# other.net
KiCad netlist of a schematic drawn in Altium Designer
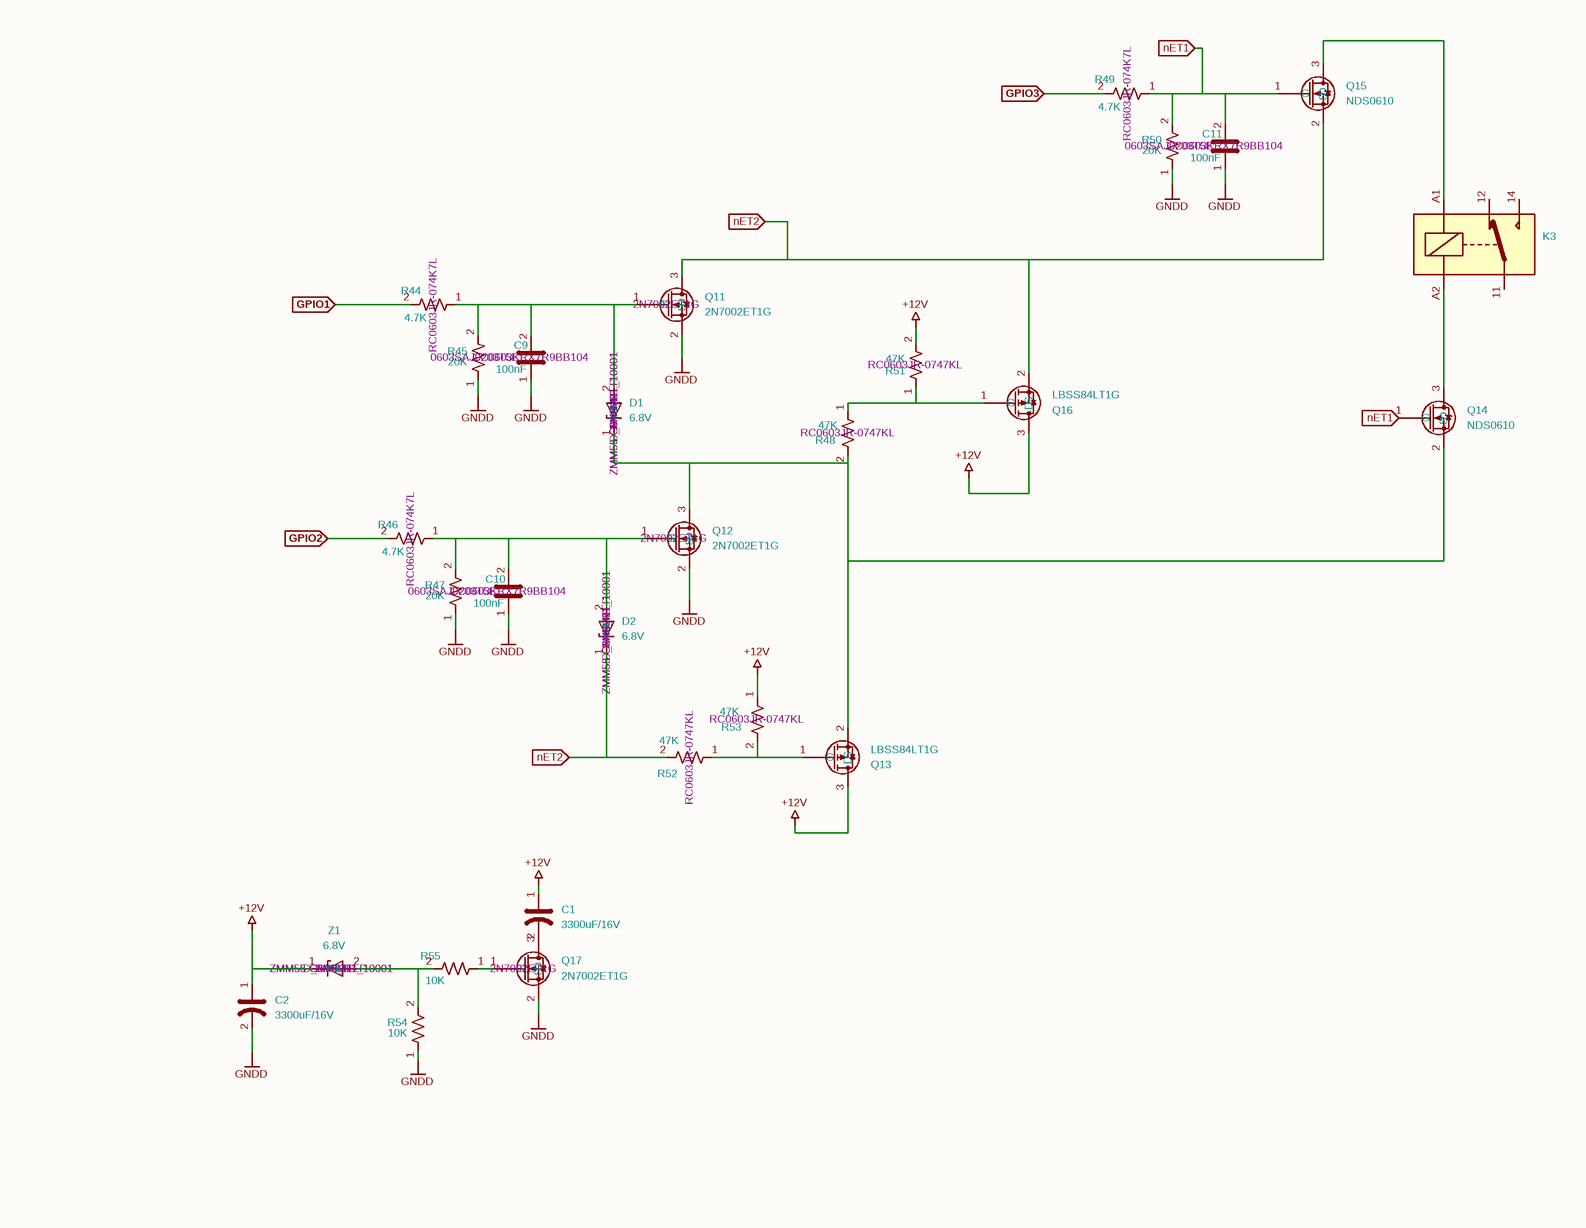
[diagram p0: other.SchDoc, left]
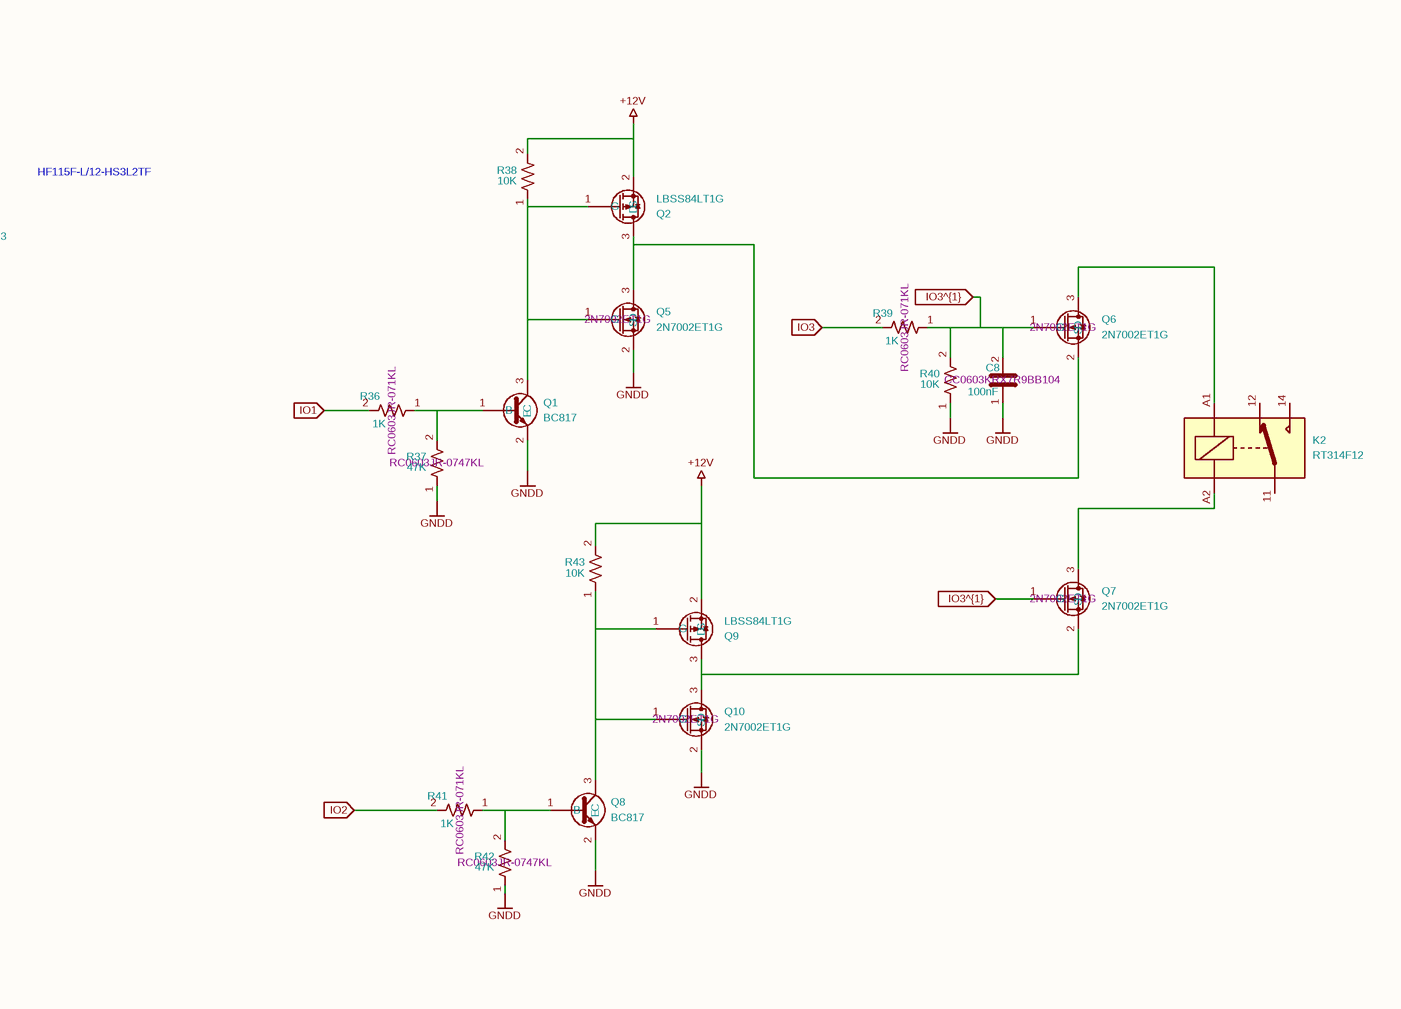
[diagram p1: other.SchDoc, right]

(export (version "E")
  (design (tool "Eeschema 10.0.6"))
  (components
    (comp (ref "C1")
      (value "3300uF/16V")
      (description "capacitor, US symbol")
      (libsource (lib "Device") (part "C_US"))
    )
    (comp (ref "C2")
      (value "3300uF/16V")
      (description "capacitor, US symbol")
      (libsource (lib "Device") (part "C_US"))
    )
    (comp (ref "C8")
      (value "100nF")
      (footprint "C_0603_1608Metric")
      (description "CAP CER 100nF 50V X7R 0603")
      (fields
        (field (name "MP") "CC0603KRX7R9BB104")
        (field (name "MF") "YAGEO")
        (field (name "OZD") "CC0603KRX7R9BB104")
      )
      (libsource (lib "*") (part "C_3"))
    )
    (comp (ref "C9")
      (value "100nF")
      (footprint "C_0603_1608Metric")
      (description "CAP CER 100nF 50V X7R 0603")
      (fields
        (field (name "MP") "CC0603KRX7R9BB104")
        (field (name "MF") "YAGEO")
        (field (name "OZD") "CC0603KRX7R9BB104")
      )
      (libsource (lib "*") (part "C_3"))
    )
    (comp (ref "C10")
      (value "100nF")
      (footprint "C_0603_1608Metric")
      (description "CAP CER 100nF 50V X7R 0603")
      (fields
        (field (name "MP") "CC0603KRX7R9BB104")
        (field (name "MF") "YAGEO")
        (field (name "OZD") "CC0603KRX7R9BB104")
      )
      (libsource (lib "*") (part "C_3"))
    )
    (comp (ref "C11")
      (value "100nF")
      (footprint "C_0603_1608Metric")
      (description "CAP CER 100nF 50V X7R 0603")
      (fields
        (field (name "MP") "CC0603KRX7R9BB104")
        (field (name "MF") "YAGEO")
        (field (name "OZD") "CC0603KRX7R9BB104")
      )
      (libsource (lib "*") (part "C_3"))
    )
    (comp (ref "D1")
      (value "6.8V")
      (description "DIODE ZENER 500mW 6.8V ±5% SOD80 (MINIMELF) SMT")
      (fields
        (field (name "MF") "PANJIT")
        (field (name "MP") "ZMM55-C6V8_R1_10001")
        (field (name "OZD") "ZMM55-C6V8_R1_10001")
        (field (name "PACKAGE") "D_MiniMELF")
      )
      (libsource (lib "*") (part "D_Zener_1"))
    )
    (comp (ref "D2")
      (value "6.8V")
      (description "DIODE ZENER 500mW 6.8V ±5% SOD80 (MINIMELF) SMT")
      (fields
        (field (name "MF") "PANJIT")
        (field (name "MP") "ZMM55-C6V8_R1_10001")
        (field (name "OZD") "ZMM55-C6V8_R1_10001")
        (field (name "PACKAGE") "D_MiniMELF")
      )
      (libsource (lib "Device") (part "D_Zener"))
    )
    (comp (ref "K2")
      (value "RT314F12")
      (footprint "RELAY9-500X1142_618")
      (description "RELAY POWER SPDT-CO 16A 12V")
      (fields (field (name "MF") "TE Connectivity"))
      (libsource (lib "*") (part "RT314A03_1"))
    )
    (comp (ref "K3")
      (value "RT314F12")
      (footprint "RELAY9-500X1142_618")
      (description "RELAY POWER SPDT-CO 16A 12V")
      (fields (field (name "MF") "TE Connectivity"))
      (libsource (lib "*") (part "RT314A03_1"))
    )
    (comp (ref "Q1")
      (value "BC817")
      (footprint "SOT-23")
      (description "0.8A Ic, 45V Vce, NPN Transistor, SOT-23")
      (libsource (lib "Transistor_BJT") (part "BC817"))
    )
    (comp (ref "Q2")
      (value "LBSS84LT1G")
      (footprint "SOT-23")
      (description "P-MOSFET transistor, gate/source/drain")
      (libsource (lib "Transistor_FET") (part "Q_PMOS_GSD"))
    )
    (comp (ref "Q5")
      (value "2N7002ET1G")
      (footprint "SOT-23")
      (description "MOSFET N-CH 60V 310mA SOT-23")
      (fields (field (name "MF") "onsemi") (field (name "OZD") "2N7002ET1G"))
      (libsource (lib "Transistor_FET_Other") (part "Q_NMOS_Depletion_GSD"))
    )
    (comp (ref "Q6")
      (value "2N7002ET1G")
      (footprint "SOT-23")
      (description "MOSFET N-CH 60V 310mA SOT-23")
      (fields (field (name "MF") "onsemi") (field (name "OZD") "2N7002ET1G"))
      (libsource (lib "Transistor_FET_Other") (part "Q_NMOS_Depletion_GSD"))
    )
    (comp (ref "Q7")
      (value "2N7002ET1G")
      (footprint "SOT-23")
      (description "MOSFET N-CH 60V 310mA SOT-23")
      (fields (field (name "MF") "onsemi") (field (name "OZD") "2N7002ET1G"))
      (libsource (lib "Transistor_FET_Other") (part "Q_NMOS_Depletion_GSD"))
    )
    (comp (ref "Q8")
      (value "BC817")
      (footprint "SOT-23")
      (description "0.8A Ic, 45V Vce, NPN Transistor, SOT-23")
      (libsource (lib "Transistor_BJT") (part "BC817"))
    )
    (comp (ref "Q9")
      (value "LBSS84LT1G")
      (footprint "SOT-23")
      (description "P-MOSFET transistor, gate/source/drain")
      (libsource (lib "Transistor_FET") (part "Q_PMOS_GSD"))
    )
    (comp (ref "Q10")
      (value "2N7002ET1G")
      (footprint "SOT-23")
      (description "MOSFET N-CH 60V 310mA SOT-23")
      (fields (field (name "MF") "onsemi") (field (name "OZD") "2N7002ET1G"))
      (libsource (lib "Transistor_FET_Other") (part "Q_NMOS_Depletion_GSD"))
    )
    (comp (ref "Q11")
      (value "2N7002ET1G")
      (footprint "SOT-23")
      (description "MOSFET N-CH 60V 310mA SOT-23")
      (fields (field (name "MF") "onsemi") (field (name "OZD") "2N7002ET1G"))
      (libsource (lib "Transistor_FET_Other") (part "Q_NMOS_Depletion_GSD"))
    )
    (comp (ref "Q12")
      (value "2N7002ET1G")
      (footprint "SOT-23")
      (description "MOSFET N-CH 60V 310mA SOT-23")
      (fields (field (name "MF") "onsemi") (field (name "OZD") "2N7002ET1G"))
      (libsource (lib "Transistor_FET_Other") (part "Q_NMOS_Depletion_GSD"))
    )
    (comp (ref "Q13")
      (value "LBSS84LT1G")
      (footprint "SOT-23")
      (description "P-MOSFET transistor, gate/source/drain")
      (libsource (lib "Transistor_FET") (part "Q_PMOS_GSD"))
    )
    (comp (ref "Q14")
      (value "NDS0610")
      (footprint "SOT-23")
      (libsource (lib "Transistor_FET_Other") (part "Q_NMOS_Depletion_GSD"))
    )
    (comp (ref "Q15")
      (value "NDS0610")
      (footprint "SOT-23")
      (libsource (lib "Transistor_FET_Other") (part "Q_NMOS_Depletion_GSD"))
    )
    (comp (ref "Q16")
      (value "LBSS84LT1G")
      (footprint "SOT-23")
      (description "P-MOSFET transistor, gate/source/drain")
      (libsource (lib "*") (part "Q_PMOS_GSD_1"))
    )
    (comp (ref "Q17")
      (value "2N7002ET1G")
      (footprint "SOT-23")
      (description "MOSFET N-CH 60V 310mA SOT-23")
      (fields (field (name "MF") "onsemi") (field (name "OZD") "2N7002ET1G"))
      (libsource (lib "Transistor_FET_Other") (part "Q_NMOS_Depletion_GSD"))
    )
    (comp (ref "R36")
      (value "1K")
      (footprint "R_0603_1608Metric")
      (description "RES 1kΩ ±5% 100mW 0603")
      (fields
        (field (name "MP") "RC0603JR-071KL")
        (field (name "MF") "YAGEO")
        (field (name "OZD") "RC0603JR-071KL")
      )
      (libsource (lib "Device") (part "R_US"))
    )
    (comp (ref "R37")
      (value "47K")
      (footprint "R_0603_1608Metric")
      (description "RES 47kΩ ±5% 100mW 0603")
      (fields
        (field (name "MP") "RC0603JR-0747KL")
        (field (name "MF") "YAGEO")
        (field (name "OZD") "RC0603JR-0747KL")
      )
      (libsource (lib "Device") (part "R_US"))
    )
    (comp (ref "R38")
      (value "10K")
      (footprint "R_0603_1608Metric")
      (description "100mW Thick Film Resistors 75V ±100ppm/℃ ±5% 10kΩ 0603 Chip Resistor - Surface Mount ROHS")
      (fields (field (name "MP") "FRC0603J103TS") (field (name "MF") "FOJAN"))
      (libsource (lib "Device") (part "R_US"))
    )
    (comp (ref "R39")
      (value "1K")
      (footprint "R_0603_1608Metric")
      (description "RES 1kΩ ±5% 100mW 0603")
      (fields
        (field (name "MP") "RC0603JR-071KL")
        (field (name "MF") "YAGEO")
        (field (name "OZD") "RC0603JR-071KL")
      )
      (libsource (lib "Device") (part "R_US"))
    )
    (comp (ref "R40")
      (value "10K")
      (footprint "R_0603_1608Metric")
      (description "100mW Thick Film Resistors 75V ±100ppm/℃ ±5% 10kΩ 0603 Chip Resistor - Surface Mount ROHS")
      (fields (field (name "MP") "FRC0603J103TS") (field (name "MF") "FOJAN"))
      (libsource (lib "Device") (part "R_US"))
    )
    (comp (ref "R41")
      (value "1K")
      (footprint "R_0603_1608Metric")
      (description "RES 1kΩ ±5% 100mW 0603")
      (fields
        (field (name "MP") "RC0603JR-071KL")
        (field (name "MF") "YAGEO")
        (field (name "OZD") "RC0603JR-071KL")
      )
      (libsource (lib "Device") (part "R_US"))
    )
    (comp (ref "R42")
      (value "47K")
      (footprint "R_0603_1608Metric")
      (description "RES 47kΩ ±5% 100mW 0603")
      (fields
        (field (name "MP") "RC0603JR-0747KL")
        (field (name "MF") "YAGEO")
        (field (name "OZD") "RC0603JR-0747KL")
      )
      (libsource (lib "Device") (part "R_US"))
    )
    (comp (ref "R43")
      (value "10K")
      (footprint "R_0603_1608Metric")
      (description "100mW Thick Film Resistors 75V ±100ppm/℃ ±5% 10kΩ 0603 Chip Resistor - Surface Mount ROHS")
      (fields (field (name "MP") "FRC0603J103TS") (field (name "MF") "FOJAN"))
      (libsource (lib "Device") (part "R_US"))
    )
    (comp (ref "R44")
      (value "4.7K")
      (footprint "R_0603_1608Metric")
      (description "RES 4.7kΩ ±5% 100mW 0603")
      (fields
        (field (name "MP") "RC0603JR-074K7L")
        (field (name "MF") "YAGEO")
        (field (name "OZD") "RC0603JR-074K7L")
      )
      (libsource (lib "Device") (part "R_US"))
    )
    (comp (ref "R45")
      (value "20K")
      (footprint "R_0603_1608Metric")
      (description "RES.(1608) 0603 20K Ohms 5% 1/10W-S 100PPM")
      (fields
        (field (name "MP") "0603SAJ0203T5E")
        (field (name "MF") "ROYALOHM")
        (field (name "OZD") "0603SAJ0203T5E")
      )
      (libsource (lib "Device") (part "R_US"))
    )
    (comp (ref "R46")
      (value "4.7K")
      (footprint "R_0603_1608Metric")
      (description "RES 4.7kΩ ±5% 100mW 0603")
      (fields
        (field (name "MP") "RC0603JR-074K7L")
        (field (name "MF") "YAGEO")
        (field (name "OZD") "RC0603JR-074K7L")
      )
      (libsource (lib "Device") (part "R_US"))
    )
    (comp (ref "R47")
      (value "20K")
      (footprint "R_0603_1608Metric")
      (description "RES.(1608) 0603 20K Ohms 5% 1/10W-S 100PPM")
      (fields
        (field (name "MP") "0603SAJ0203T5E")
        (field (name "MF") "ROYALOHM")
        (field (name "OZD") "0603SAJ0203T5E")
      )
      (libsource (lib "Device") (part "R_US"))
    )
    (comp (ref "R48")
      (value "47K")
      (footprint "R_0603_1608Metric")
      (description "RES 47kΩ ±5% 100mW 0603")
      (fields
        (field (name "MP") "RC0603JR-0747KL")
        (field (name "MF") "YAGEO")
        (field (name "OZD") "RC0603JR-0747KL")
      )
      (libsource (lib "Device") (part "R_US"))
    )
    (comp (ref "R49")
      (value "4.7K")
      (footprint "R_0603_1608Metric")
      (description "RES 4.7kΩ ±5% 100mW 0603")
      (fields
        (field (name "MP") "RC0603JR-074K7L")
        (field (name "MF") "YAGEO")
        (field (name "OZD") "RC0603JR-074K7L")
      )
      (libsource (lib "Device") (part "R_US"))
    )
    (comp (ref "R50")
      (value "20K")
      (footprint "R_0603_1608Metric")
      (description "RES.(1608) 0603 20K Ohms 5% 1/10W-S 100PPM")
      (fields
        (field (name "MP") "0603SAJ0203T5E")
        (field (name "MF") "ROYALOHM")
        (field (name "OZD") "0603SAJ0203T5E")
      )
      (libsource (lib "Device") (part "R_US"))
    )
    (comp (ref "R51")
      (value "47K")
      (footprint "R_0603_1608Metric")
      (description "RES 47kΩ ±5% 100mW 0603")
      (fields
        (field (name "MP") "RC0603JR-0747KL")
        (field (name "MF") "YAGEO")
        (field (name "OZD") "RC0603JR-0747KL")
      )
      (libsource (lib "Device") (part "R_US"))
    )
    (comp (ref "R52")
      (value "47K")
      (footprint "R_0603_1608Metric")
      (description "RES 47kΩ ±5% 100mW 0603")
      (fields
        (field (name "MP") "RC0603JR-0747KL")
        (field (name "MF") "YAGEO")
        (field (name "OZD") "RC0603JR-0747KL")
      )
      (libsource (lib "Device") (part "R_US"))
    )
    (comp (ref "R53")
      (value "47K")
      (footprint "R_0603_1608Metric")
      (description "RES 47kΩ ±5% 100mW 0603")
      (fields
        (field (name "MP") "RC0603JR-0747KL")
        (field (name "MF") "YAGEO")
        (field (name "OZD") "RC0603JR-0747KL")
      )
      (libsource (lib "Device") (part "R_US"))
    )
    (comp (ref "R54")
      (value "10K")
      (footprint "R_0603_1608Metric")
      (description "100mW Thick Film Resistors 75V ±100ppm/℃ ±5% 10kΩ 0603 Chip Resistor - Surface Mount ROHS")
      (fields (field (name "MP") "FRC0603J103TS") (field (name "MF") "FOJAN"))
      (libsource (lib "Device") (part "R_US"))
    )
    (comp (ref "R55")
      (value "10K")
      (footprint "R_0603_1608Metric")
      (description "100mW Thick Film Resistors 75V ±100ppm/℃ ±5% 10kΩ 0603 Chip Resistor - Surface Mount ROHS")
      (fields (field (name "MP") "FRC0603J103TS") (field (name "MF") "FOJAN"))
      (libsource (lib "Device") (part "R_US"))
    )
    (comp (ref "Z1")
      (value "6.8V")
      (description "DIODE ZENER 500mW 6.8V ±5% SOD80 (MINIMELF) SMT")
      (fields
        (field (name "MF") "PANJIT")
        (field (name "MP") "ZMM55-C6V8_R1_10001")
        (field (name "OZD") "ZMM55-C6V8_R1_10001")
        (field (name "PACKAGE") "D_MiniMELF")
      )
      (libsource (lib "Device") (part "D_Zener"))
    )
  )
  (nets
    (net (code "1") (name "+12V") (class "Default")
      (node (ref "C1") (pin "1") (pinfunction "1_1") (pintype "passive"))
      (node (ref "C2") (pin "1") (pinfunction "1_1") (pintype "passive"))
      (node (ref "Q13") (pin "3") (pinfunction "D_3") (pintype "passive"))
      (node (ref "Q16") (pin "3") (pinfunction "D_3") (pintype "passive"))
      (node (ref "Q2") (pin "2") (pinfunction "S_2") (pintype "passive"))
      (node (ref "Q9") (pin "2") (pinfunction "S_2") (pintype "passive"))
      (node (ref "R38") (pin "2") (pinfunction "2_2") (pintype "passive"))
      (node (ref "R43") (pin "2") (pinfunction "2_2") (pintype "passive"))
      (node (ref "R51") (pin "2") (pinfunction "2_2") (pintype "passive"))
      (node (ref "R53") (pin "1") (pinfunction "1_1") (pintype "passive"))
      (node (ref "Z1") (pin "1") (pinfunction "K_1") (pintype "passive"))
    )
    (net (code "2") (name "/GPIO1") (class "Default")
      (node (ref "R44") (pin "2") (pinfunction "2_2") (pintype "passive"))
    )
    (net (code "3") (name "/GPIO2") (class "Default")
      (node (ref "R46") (pin "2") (pinfunction "2_2") (pintype "passive"))
    )
    (net (code "4") (name "/GPIO3") (class "Default")
      (node (ref "R49") (pin "2") (pinfunction "2_2") (pintype "passive"))
    )
    (net (code "5") (name "/IO1") (class "Default")
      (node (ref "R36") (pin "2") (pinfunction "2_2") (pintype "passive"))
    )
    (net (code "6") (name "/IO2") (class "Default")
      (node (ref "R41") (pin "2") (pinfunction "2_2") (pintype "passive"))
    )
    (net (code "7") (name "/IO3") (class "Default")
      (node (ref "R39") (pin "2") (pinfunction "2_2") (pintype "passive"))
    )
    (net (code "8") (name "/IO3^{1}") (class "Default")
      (node (ref "C8") (pin "2") (pinfunction "2_2") (pintype "passive"))
      (node (ref "Q6") (pin "1") (pinfunction "G_1") (pintype "passive"))
      (node (ref "Q7") (pin "1") (pinfunction "G_1") (pintype "passive"))
      (node (ref "R39") (pin "1") (pinfunction "1_1") (pintype "passive"))
      (node (ref "R40") (pin "2") (pinfunction "2_2") (pintype "passive"))
    )
    (net (code "9") (name "/nET1") (class "Default")
      (node (ref "C11") (pin "2") (pinfunction "2_2") (pintype "passive"))
      (node (ref "Q14") (pin "1") (pinfunction "G_1") (pintype "passive"))
      (node (ref "Q15") (pin "1") (pinfunction "G_1") (pintype "passive"))
      (node (ref "R49") (pin "1") (pinfunction "1_1") (pintype "passive"))
      (node (ref "R50") (pin "2") (pinfunction "2_2") (pintype "passive"))
    )
    (net (code "10") (name "/nET2") (class "Default")
      (node (ref "D2") (pin "1") (pinfunction "K_1") (pintype "passive"))
      (node (ref "Q11") (pin "3") (pinfunction "D_3") (pintype "passive"))
      (node (ref "Q15") (pin "2") (pinfunction "S_2") (pintype "passive"))
      (node (ref "Q16") (pin "2") (pinfunction "S_2") (pintype "passive"))
      (node (ref "R52") (pin "2") (pinfunction "2_2") (pintype "passive"))
    )
    (net (code "11") (name "GNDD") (class "Default")
      (node (ref "C10") (pin "1") (pinfunction "1_1") (pintype "passive"))
      (node (ref "C11") (pin "1") (pinfunction "1_1") (pintype "passive"))
      (node (ref "C2") (pin "2") (pinfunction "2_2") (pintype "passive"))
      (node (ref "C8") (pin "1") (pinfunction "1_1") (pintype "passive"))
      (node (ref "C9") (pin "1") (pinfunction "1_1") (pintype "passive"))
      (node (ref "Q1") (pin "2") (pinfunction "E_2") (pintype "passive"))
      (node (ref "Q10") (pin "2") (pinfunction "S_2") (pintype "passive"))
      (node (ref "Q11") (pin "2") (pinfunction "S_2") (pintype "passive"))
      (node (ref "Q12") (pin "2") (pinfunction "S_2") (pintype "passive"))
      (node (ref "Q17") (pin "2") (pinfunction "S_2") (pintype "passive"))
      (node (ref "Q5") (pin "2") (pinfunction "S_2") (pintype "passive"))
      (node (ref "Q8") (pin "2") (pinfunction "E_2") (pintype "passive"))
      (node (ref "R37") (pin "1") (pinfunction "1_1") (pintype "passive"))
      (node (ref "R40") (pin "1") (pinfunction "1_1") (pintype "passive"))
      (node (ref "R42") (pin "1") (pinfunction "1_1") (pintype "passive"))
      (node (ref "R45") (pin "1") (pinfunction "1_1") (pintype "passive"))
      (node (ref "R47") (pin "1") (pinfunction "1_1") (pintype "passive"))
      (node (ref "R50") (pin "1") (pinfunction "1_1") (pintype "passive"))
      (node (ref "R54") (pin "1") (pinfunction "1_1") (pintype "passive"))
    )
    (net (code "12") (name "Net-(D1-A)") (class "Default")
      (node (ref "C9") (pin "2") (pinfunction "2_2") (pintype "passive"))
      (node (ref "D1") (pin "2") (pinfunction "A_2") (pintype "passive"))
      (node (ref "Q11") (pin "1") (pinfunction "G_1") (pintype "passive"))
      (node (ref "R44") (pin "1") (pinfunction "1_1") (pintype "passive"))
      (node (ref "R45") (pin "2") (pinfunction "2_2") (pintype "passive"))
    )
    (net (code "13") (name "Net-(D1-K)") (class "Default")
      (node (ref "D1") (pin "1") (pinfunction "K_1") (pintype "passive"))
      (node (ref "Q12") (pin "3") (pinfunction "D_3") (pintype "passive"))
      (node (ref "Q13") (pin "2") (pinfunction "S_2") (pintype "passive"))
      (node (ref "Q14") (pin "2") (pinfunction "S_2") (pintype "passive"))
      (node (ref "R48") (pin "2") (pinfunction "2_2") (pintype "passive"))
    )
    (net (code "14") (name "Net-(D2-A)") (class "Default")
      (node (ref "C10") (pin "2") (pinfunction "2_2") (pintype "passive"))
      (node (ref "D2") (pin "2") (pinfunction "A_2") (pintype "passive"))
      (node (ref "Q12") (pin "1") (pinfunction "G_1") (pintype "passive"))
      (node (ref "R46") (pin "1") (pinfunction "1_1") (pintype "passive"))
      (node (ref "R47") (pin "2") (pinfunction "2_2") (pintype "passive"))
    )
    (net (code "15") (name "Net-(Q1-B)") (class "Default")
      (node (ref "Q1") (pin "1") (pinfunction "B_1") (pintype "passive"))
      (node (ref "R36") (pin "1") (pinfunction "1_1") (pintype "passive"))
      (node (ref "R37") (pin "2") (pinfunction "2_2") (pintype "passive"))
    )
    (net (code "16") (name "Net-(Q1-C)") (class "Default")
      (node (ref "Q1") (pin "3") (pinfunction "C_3") (pintype "passive"))
      (node (ref "Q2") (pin "1") (pinfunction "G_1") (pintype "passive"))
      (node (ref "Q5") (pin "1") (pinfunction "G_1") (pintype "passive"))
      (node (ref "R38") (pin "1") (pinfunction "1_1") (pintype "passive"))
    )
    (net (code "17") (name "Net-(Q2-D)") (class "Default")
      (node (ref "Q2") (pin "3") (pinfunction "D_3") (pintype "passive"))
      (node (ref "Q5") (pin "3") (pinfunction "D_3") (pintype "passive"))
      (node (ref "Q6") (pin "2") (pinfunction "S_2") (pintype "passive"))
    )
    (net (code "18") (name "Net-(Q6-D)") (class "Default")
      (node (ref "K2") (pin "A1") (pinfunction "A1_A1") (pintype "passive"))
      (node (ref "Q6") (pin "3") (pinfunction "D_3") (pintype "passive"))
    )
    (net (code "19") (name "Net-(Q7-D)") (class "Default")
      (node (ref "K2") (pin "A2") (pinfunction "A2_A2") (pintype "passive"))
      (node (ref "Q7") (pin "3") (pinfunction "D_3") (pintype "passive"))
    )
    (net (code "20") (name "Net-(Q8-B)") (class "Default")
      (node (ref "Q8") (pin "1") (pinfunction "B_1") (pintype "passive"))
      (node (ref "R41") (pin "1") (pinfunction "1_1") (pintype "passive"))
      (node (ref "R42") (pin "2") (pinfunction "2_2") (pintype "passive"))
    )
    (net (code "21") (name "Net-(Q10-D)") (class "Default")
      (node (ref "Q10") (pin "3") (pinfunction "D_3") (pintype "passive"))
      (node (ref "Q7") (pin "2") (pinfunction "S_2") (pintype "passive"))
      (node (ref "Q9") (pin "3") (pinfunction "D_3") (pintype "passive"))
    )
    (net (code "22") (name "Net-(Q10-G)") (class "Default")
      (node (ref "Q10") (pin "1") (pinfunction "G_1") (pintype "passive"))
      (node (ref "Q8") (pin "3") (pinfunction "C_3") (pintype "passive"))
      (node (ref "Q9") (pin "1") (pinfunction "G_1") (pintype "passive"))
      (node (ref "R43") (pin "1") (pinfunction "1_1") (pintype "passive"))
    )
    (net (code "23") (name "Net-(Q13-G)") (class "Default")
      (node (ref "Q13") (pin "1") (pinfunction "G_1") (pintype "passive"))
      (node (ref "R52") (pin "1") (pinfunction "1_1") (pintype "passive"))
      (node (ref "R53") (pin "2") (pinfunction "2_2") (pintype "passive"))
    )
    (net (code "24") (name "Net-(Q14-D)") (class "Default")
      (node (ref "K3") (pin "A2") (pinfunction "A2_A2") (pintype "passive"))
      (node (ref "Q14") (pin "3") (pinfunction "D_3") (pintype "passive"))
    )
    (net (code "25") (name "Net-(Q15-D)") (class "Default")
      (node (ref "K3") (pin "A1") (pinfunction "A1_A1") (pintype "passive"))
      (node (ref "Q15") (pin "3") (pinfunction "D_3") (pintype "passive"))
    )
    (net (code "26") (name "Net-(Q16-G)") (class "Default")
      (node (ref "Q16") (pin "1") (pinfunction "G_1") (pintype "passive"))
      (node (ref "R48") (pin "1") (pinfunction "1_1") (pintype "passive"))
      (node (ref "R51") (pin "1") (pinfunction "1_1") (pintype "passive"))
    )
    (net (code "27") (name "Net-(Q17-D)") (class "Default")
      (node (ref "C1") (pin "2") (pinfunction "2_2") (pintype "passive"))
      (node (ref "Q17") (pin "3") (pinfunction "D_3") (pintype "passive"))
    )
    (net (code "28") (name "Net-(Q17-G)") (class "Default")
      (node (ref "Q17") (pin "1") (pinfunction "G_1") (pintype "passive"))
      (node (ref "R55") (pin "1") (pinfunction "1_1") (pintype "passive"))
    )
    (net (code "29") (name "Net-(Z1-A)") (class "Default")
      (node (ref "R54") (pin "2") (pinfunction "2_2") (pintype "passive"))
      (node (ref "R55") (pin "2") (pinfunction "2_2") (pintype "passive"))
      (node (ref "Z1") (pin "2") (pinfunction "A_2") (pintype "passive"))
    )
    (net (code "30") (name "unconnected-(K2-Pad11)") (class "Default")
      (node (ref "K2") (pin "11") (pinfunction "11_11") (pintype "passive"))
    )
    (net (code "31") (name "unconnected-(K2-Pad12)") (class "Default")
      (node (ref "K2") (pin "12") (pinfunction "12_12") (pintype "passive"))
    )
    (net (code "32") (name "unconnected-(K2-Pad14)") (class "Default")
      (node (ref "K2") (pin "14") (pinfunction "14_14") (pintype "passive"))
    )
    (net (code "33") (name "unconnected-(K3-Pad11)") (class "Default")
      (node (ref "K3") (pin "11") (pinfunction "11_11") (pintype "passive"))
    )
    (net (code "34") (name "unconnected-(K3-Pad12)") (class "Default")
      (node (ref "K3") (pin "12") (pinfunction "12_12") (pintype "passive"))
    )
    (net (code "35") (name "unconnected-(K3-Pad14)") (class "Default")
      (node (ref "K3") (pin "14") (pinfunction "14_14") (pintype "passive"))
    )
  )
)
